# expansion.net
KiCad netlist of a schematic drawn in EAGLE
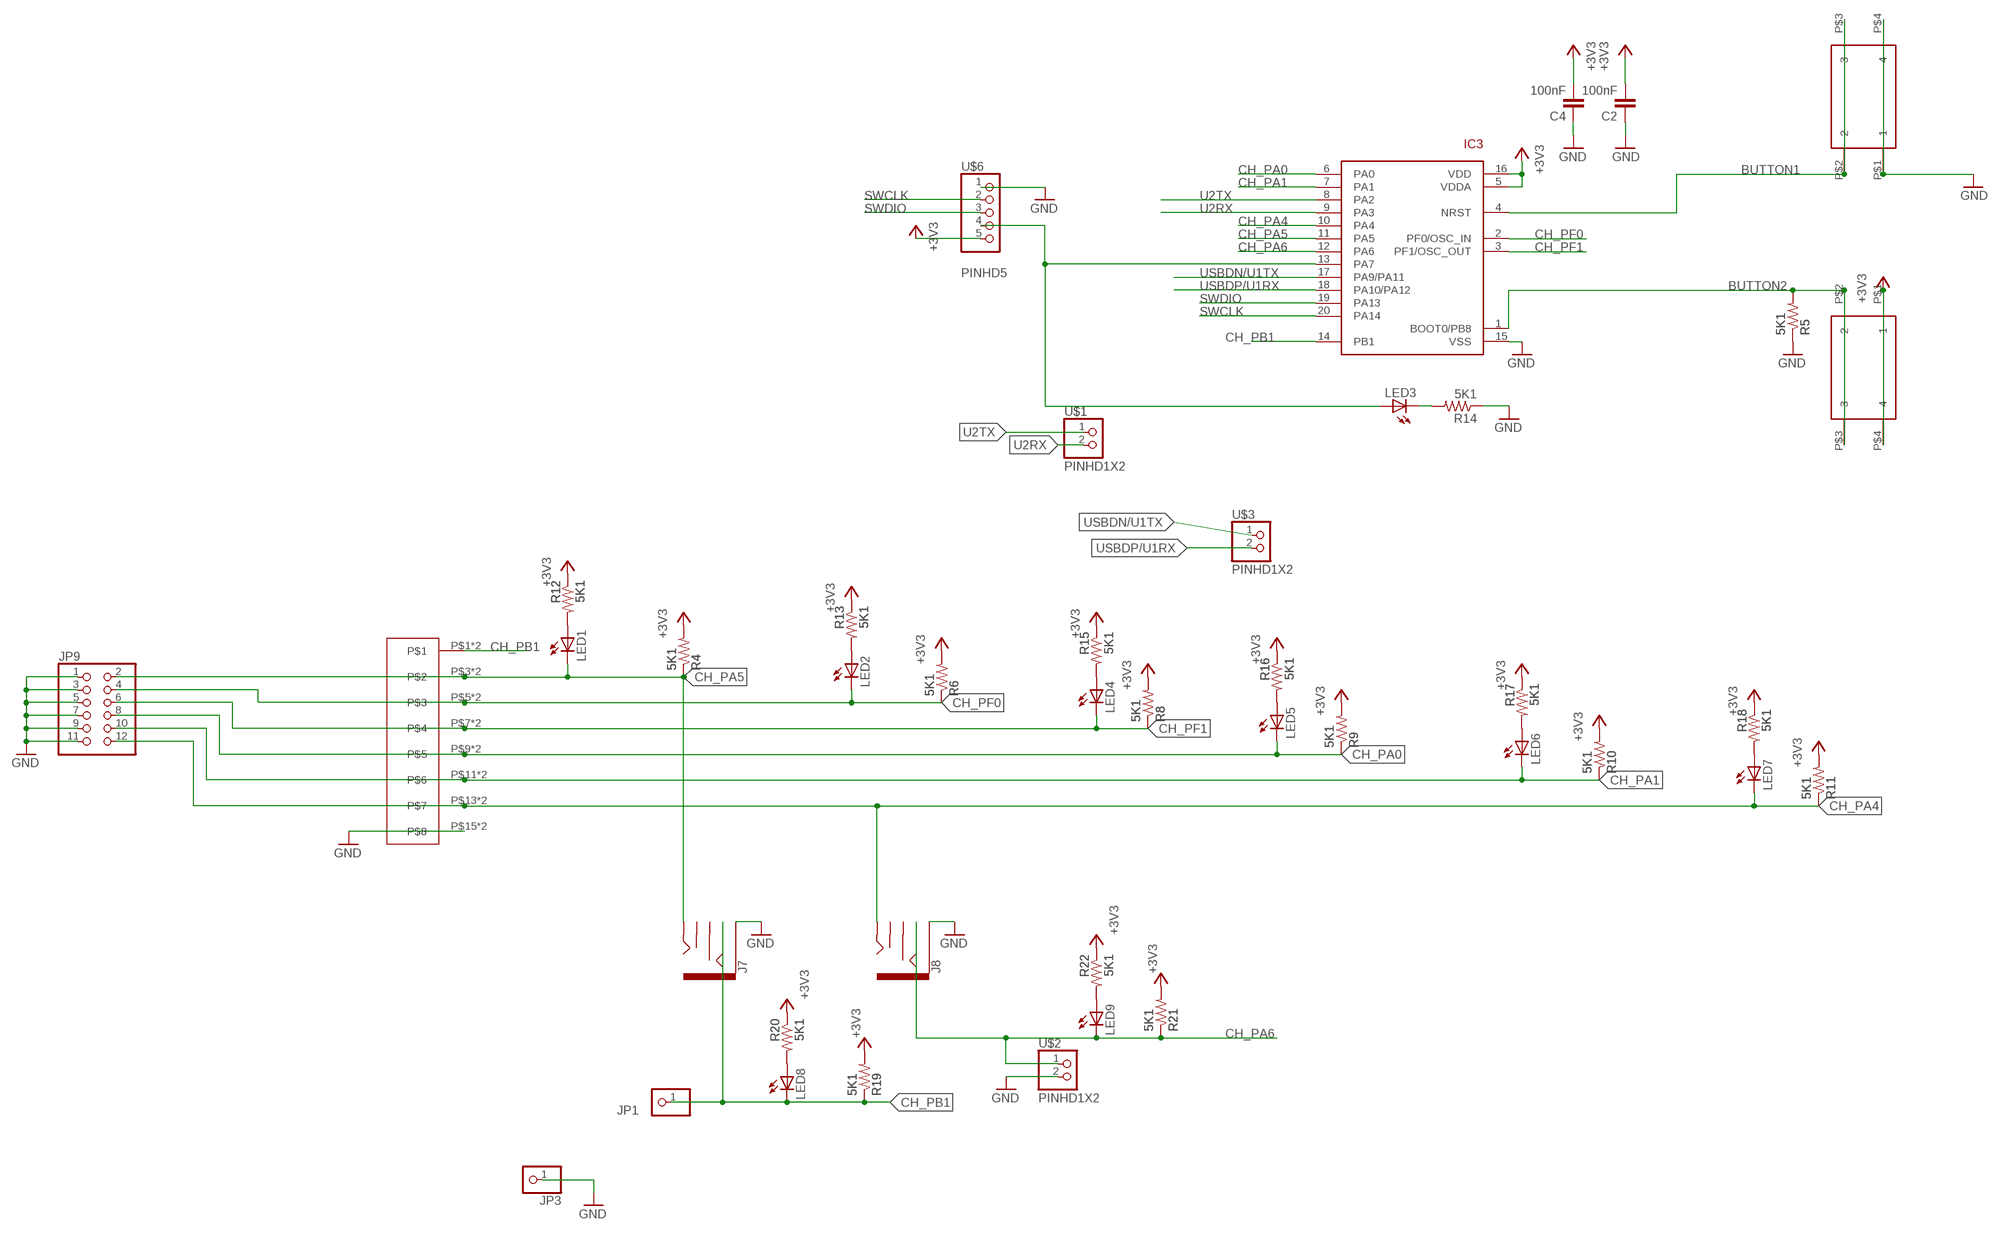
[diagram p0: schematic, sheet 1, part 1 of 2]
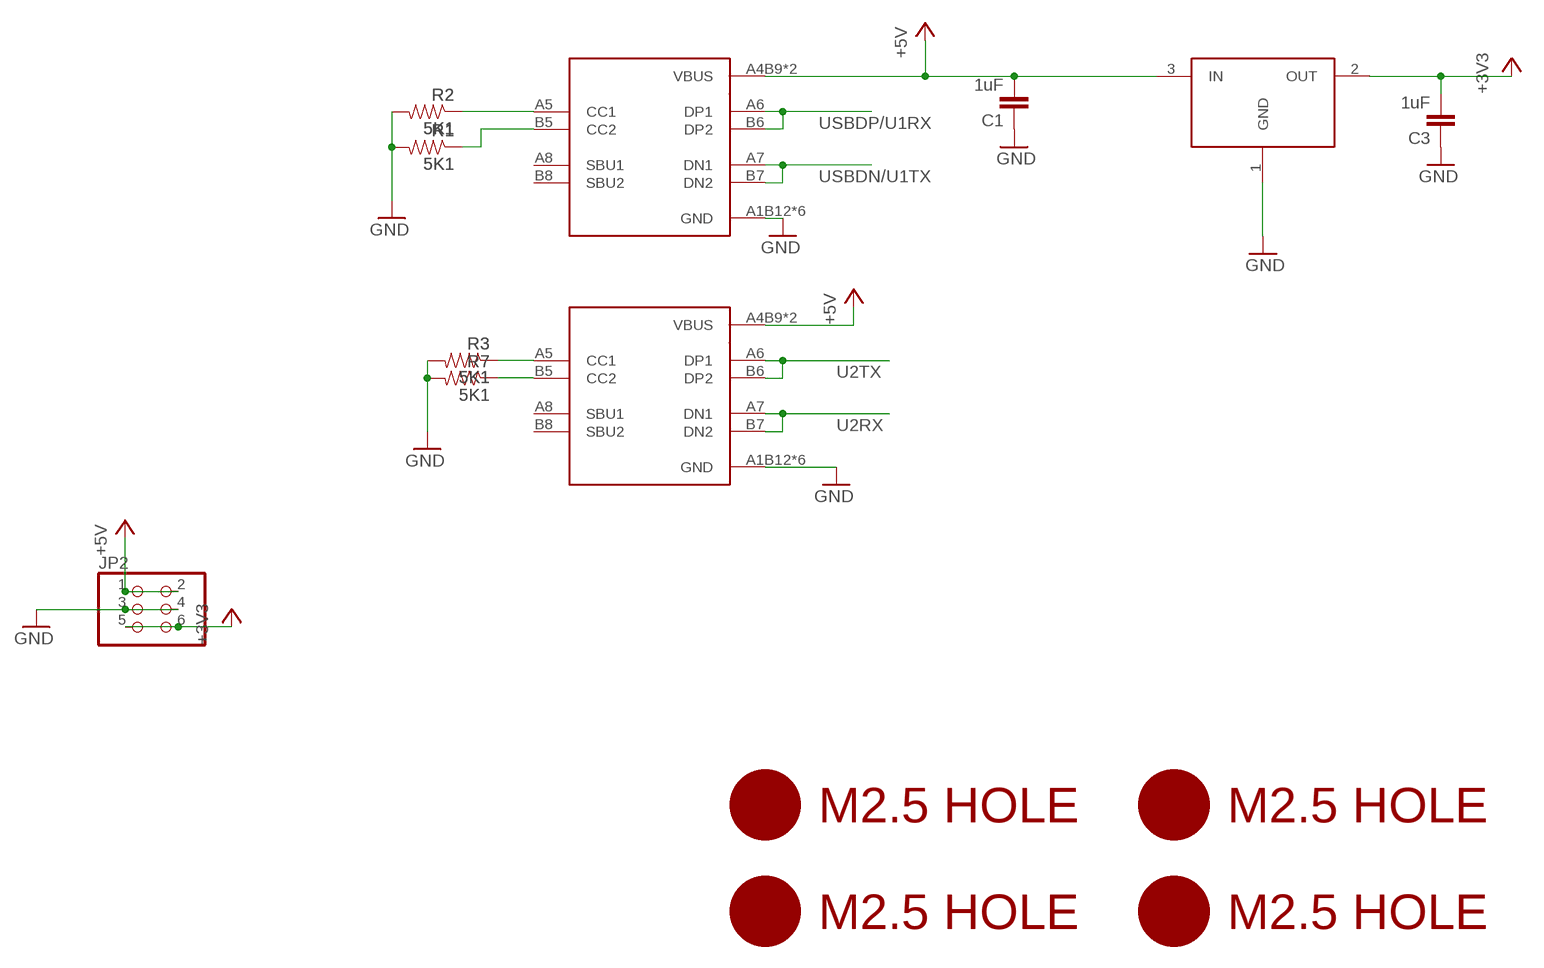
[diagram p1: schematic, sheet 1, part 2 of 2]

(export (version "E")
  (design (tool "Eeschema 10.0.6"))
  (components
    (comp (ref "C1")
      (value "1uF")
      (footprint "eagle-import:0805")
      (libsource (lib "eagle-import") (part "CAP0805"))
    )
    (comp (ref "C2")
      (value "100nF")
      (footprint "eagle-import:0805")
      (libsource (lib "eagle-import") (part "CAP0805"))
    )
    (comp (ref "C3")
      (value "1uF")
      (footprint "eagle-import:0805")
      (libsource (lib "eagle-import") (part "CAP0805"))
    )
    (comp (ref "C4")
      (value "100nF")
      (footprint "eagle-import:0805")
      (libsource (lib "eagle-import") (part "CAP0805"))
    )
    (comp (ref "IC3")
      (value "STM32F042F4")
      (footprint "eagle-import:TSSOP20")
      (libsource (lib "eagle-import") (part "STM32F042F4"))
    )
    (comp (ref "J7")
      (value "AUDIO_JACK_3.5MM_PTH")
      (footprint "eagle-import:AUDIO-JACK")
      (libsource (lib "eagle-import") (part "AUDIO_JACK_3.5MM_PTH"))
    )
    (comp (ref "J8")
      (value "AUDIO_JACK_3.5MM_PTH")
      (footprint "eagle-import:AUDIO-JACK")
      (libsource (lib "eagle-import") (part "AUDIO_JACK_3.5MM_PTH"))
    )
    (comp (ref "JP1")
      (value "PINHD-1X1")
      (footprint "eagle-import:1X01")
      (libsource (lib "eagle-import") (part "PINHD-1X1"))
    )
    (comp (ref "JP2")
      (value "PINHD-2X3")
      (footprint "eagle-import:2X03")
      (libsource (lib "eagle-import") (part "PINHD-2X3"))
    )
    (comp (ref "JP3")
      (value "PINHD-1X1")
      (footprint "eagle-import:1X01")
      (libsource (lib "eagle-import") (part "PINHD-1X1"))
    )
    (comp (ref "JP9")
      (value "PINHD-2X6")
      (footprint "eagle-import:2X06")
      (libsource (lib "eagle-import") (part "PINHD-2X6"))
    )
    (comp (ref "LED1")
      (value "LEDCHIP-LED0805")
      (footprint "eagle-import:CHIP-LED0805")
      (libsource (lib "eagle-import") (part "LEDCHIP-LED0805"))
    )
    (comp (ref "LED2")
      (value "LEDCHIP-LED0805")
      (footprint "eagle-import:CHIP-LED0805")
      (libsource (lib "eagle-import") (part "LEDCHIP-LED0805"))
    )
    (comp (ref "LED3")
      (value "LEDCHIP-LED0805")
      (footprint "eagle-import:CHIP-LED0805")
      (libsource (lib "eagle-import") (part "LEDCHIP-LED0805"))
    )
    (comp (ref "LED4")
      (value "LEDCHIP-LED0805")
      (footprint "eagle-import:CHIP-LED0805")
      (libsource (lib "eagle-import") (part "LEDCHIP-LED0805"))
    )
    (comp (ref "LED5")
      (value "LEDCHIP-LED0805")
      (footprint "eagle-import:CHIP-LED0805")
      (libsource (lib "eagle-import") (part "LEDCHIP-LED0805"))
    )
    (comp (ref "LED6")
      (value "LEDCHIP-LED0805")
      (footprint "eagle-import:CHIP-LED0805")
      (libsource (lib "eagle-import") (part "LEDCHIP-LED0805"))
    )
    (comp (ref "LED7")
      (value "LEDCHIP-LED0805")
      (footprint "eagle-import:CHIP-LED0805")
      (libsource (lib "eagle-import") (part "LEDCHIP-LED0805"))
    )
    (comp (ref "LED8")
      (value "LEDCHIP-LED0805")
      (footprint "eagle-import:CHIP-LED0805")
      (libsource (lib "eagle-import") (part "LEDCHIP-LED0805"))
    )
    (comp (ref "LED9")
      (value "LEDCHIP-LED0805")
      (footprint "eagle-import:CHIP-LED0805")
      (libsource (lib "eagle-import") (part "LEDCHIP-LED0805"))
    )
    (comp (ref "R1")
      (value "5K1")
      (footprint "eagle-import:0805")
      (libsource (lib "eagle-import") (part "joyAnalog_RESISTOR0805-RES"))
    )
    (comp (ref "R2")
      (value "5K1")
      (footprint "eagle-import:0805")
      (libsource (lib "eagle-import") (part "joyAnalog_RESISTOR0805-RES"))
    )
    (comp (ref "R3")
      (value "5K1")
      (footprint "eagle-import:0805")
      (libsource (lib "eagle-import") (part "joyAnalog_RESISTOR0805-RES"))
    )
    (comp (ref "R4")
      (value "5K1")
      (footprint "eagle-import:0805")
      (libsource (lib "eagle-import") (part "joyAnalog_RESISTOR0805-RES"))
    )
    (comp (ref "R5")
      (value "5K1")
      (footprint "eagle-import:0805")
      (libsource (lib "eagle-import") (part "joyAnalog_RESISTOR0805-RES"))
    )
    (comp (ref "R6")
      (value "5K1")
      (footprint "eagle-import:0805")
      (libsource (lib "eagle-import") (part "joyAnalog_RESISTOR0805-RES"))
    )
    (comp (ref "R7")
      (value "5K1")
      (footprint "eagle-import:0805")
      (libsource (lib "eagle-import") (part "joyAnalog_RESISTOR0805-RES"))
    )
    (comp (ref "R8")
      (value "5K1")
      (footprint "eagle-import:0805")
      (libsource (lib "eagle-import") (part "joyAnalog_RESISTOR0805-RES"))
    )
    (comp (ref "R9")
      (value "5K1")
      (footprint "eagle-import:0805")
      (libsource (lib "eagle-import") (part "joyAnalog_RESISTOR0805-RES"))
    )
    (comp (ref "R10")
      (value "5K1")
      (footprint "eagle-import:0805")
      (libsource (lib "eagle-import") (part "joyAnalog_RESISTOR0805-RES"))
    )
    (comp (ref "R11")
      (value "5K1")
      (footprint "eagle-import:0805")
      (libsource (lib "eagle-import") (part "joyAnalog_RESISTOR0805-RES"))
    )
    (comp (ref "R12")
      (value "5K1")
      (footprint "eagle-import:0805")
      (libsource (lib "eagle-import") (part "joyAnalog_RESISTOR0805-RES"))
    )
    (comp (ref "R13")
      (value "5K1")
      (footprint "eagle-import:0805")
      (libsource (lib "eagle-import") (part "joyAnalog_RESISTOR0805-RES"))
    )
    (comp (ref "R14")
      (value "5K1")
      (footprint "eagle-import:0805")
      (libsource (lib "eagle-import") (part "RESISTOR0805-RES"))
    )
    (comp (ref "R15")
      (value "5K1")
      (footprint "eagle-import:0805")
      (libsource (lib "eagle-import") (part "joyAnalog_RESISTOR0805-RES"))
    )
    (comp (ref "R16")
      (value "5K1")
      (footprint "eagle-import:0805")
      (libsource (lib "eagle-import") (part "joyAnalog_RESISTOR0805-RES"))
    )
    (comp (ref "R17")
      (value "5K1")
      (footprint "eagle-import:0805")
      (libsource (lib "eagle-import") (part "joyAnalog_RESISTOR0805-RES"))
    )
    (comp (ref "R18")
      (value "5K1")
      (footprint "eagle-import:0805")
      (libsource (lib "eagle-import") (part "joyAnalog_RESISTOR0805-RES"))
    )
    (comp (ref "R19")
      (value "5K1")
      (footprint "eagle-import:0805")
      (libsource (lib "eagle-import") (part "joyAnalog_RESISTOR0805-RES"))
    )
    (comp (ref "R20")
      (value "5K1")
      (footprint "eagle-import:0805")
      (libsource (lib "eagle-import") (part "joyAnalog_RESISTOR0805-RES"))
    )
    (comp (ref "R21")
      (value "5K1")
      (footprint "eagle-import:0805")
      (libsource (lib "eagle-import") (part "joyAnalog_RESISTOR0805-RES"))
    )
    (comp (ref "R22")
      (value "5K1")
      (footprint "eagle-import:0805")
      (libsource (lib "eagle-import") (part "joyAnalog_RESISTOR0805-RES"))
    )
    (comp (ref "SW3")
      (value "324_SW")
      (footprint "eagle-import:342_SWICH_FOOT")
      (libsource (lib "eagle-import") (part "324_SW"))
    )
    (comp (ref "SW4")
      (value "324_SW")
      (footprint "eagle-import:342_SWICH_FOOT")
      (libsource (lib "eagle-import") (part "324_SW"))
    )
    (comp (ref "U$1")
      (value "PINHD1X2")
      (footprint "eagle-import:1X02")
      (libsource (lib "eagle-import") (part "PINHD1X2"))
    )
    (comp (ref "U$2")
      (value "PINHD1X2")
      (footprint "eagle-import:1X02")
      (libsource (lib "eagle-import") (part "PINHD1X2"))
    )
    (comp (ref "U$3")
      (value "PINHD1X2")
      (footprint "eagle-import:1X02")
      (libsource (lib "eagle-import") (part "PINHD1X2"))
    )
    (comp (ref "U$6")
      (value "PINHD5")
      (footprint "eagle-import:1X05")
      (libsource (lib "eagle-import") (part "PINHD5"))
    )
    (comp (ref "U$8")
      (value "M2.5HOLE")
      (footprint "eagle-import:M2.5HOLE")
      (libsource (lib "eagle-import") (part "M2.5HOLE"))
    )
    (comp (ref "U$9")
      (value "M2.5HOLE")
      (footprint "eagle-import:M2.5HOLE")
      (libsource (lib "eagle-import") (part "M2.5HOLE"))
    )
    (comp (ref "U$10")
      (value "M2.5HOLE")
      (footprint "eagle-import:M2.5HOLE")
      (libsource (lib "eagle-import") (part "M2.5HOLE"))
    )
    (comp (ref "U$11")
      (value "M2.5HOLE")
      (footprint "eagle-import:M2.5HOLE")
      (libsource (lib "eagle-import") (part "M2.5HOLE"))
    )
    (comp (ref "U$14")
      (value "DG2204R-5.0-8DG2204-8")
      (footprint "eagle-import:DG2204R-8-THERMAL")
      (libsource (lib "eagle-import") (part "DG2204R-5.0-8DG2204-8"))
    )
    (comp (ref "U1")
      (value "USBC_16P")
      (footprint "eagle-import:USBC_16P_FOOT")
      (libsource (lib "eagle-import") (part "USBC_16P"))
    )
    (comp (ref "U2")
      (value "USBC_16P")
      (footprint "eagle-import:USBC_16P_FOOT")
      (libsource (lib "eagle-import") (part "USBC_16P"))
    )
    (comp (ref "U4")
      (value "XC6206_DEV")
      (footprint "eagle-import:SOT23R_INFINEON")
      (libsource (lib "eagle-import") (part "XC6206_DEV"))
    )
  )
  (nets
    (net (code "1") (name "+3V3") (class "Default")
      (node (ref "C2") (pin "2") (pinfunction "2_2") (pintype "passive"))
      (node (ref "C3") (pin "2") (pinfunction "2_2") (pintype "passive"))
      (node (ref "C4") (pin "2") (pinfunction "2_2") (pintype "passive"))
      (node (ref "IC3") (pin "16") (pinfunction "VDD_16") (pintype "bidirectional"))
      (node (ref "IC3") (pin "5") (pinfunction "VDDA_5") (pintype "bidirectional"))
      (node (ref "JP2") (pin "5") (pinfunction "5_5") (pintype "passive"))
      (node (ref "JP2") (pin "6") (pinfunction "6_6") (pintype "passive"))
      (node (ref "R10") (pin "2") (pinfunction "2_2") (pintype "passive"))
      (node (ref "R11") (pin "2") (pinfunction "2_2") (pintype "passive"))
      (node (ref "R12") (pin "1") (pinfunction "1_1") (pintype "passive"))
      (node (ref "R13") (pin "1") (pinfunction "1_1") (pintype "passive"))
      (node (ref "R15") (pin "1") (pinfunction "1_1") (pintype "passive"))
      (node (ref "R16") (pin "1") (pinfunction "1_1") (pintype "passive"))
      (node (ref "R17") (pin "1") (pinfunction "1_1") (pintype "passive"))
      (node (ref "R18") (pin "1") (pinfunction "1_1") (pintype "passive"))
      (node (ref "R19") (pin "2") (pinfunction "2_2") (pintype "passive"))
      (node (ref "R20") (pin "1") (pinfunction "1_1") (pintype "passive"))
      (node (ref "R21") (pin "2") (pinfunction "2_2") (pintype "passive"))
      (node (ref "R22") (pin "1") (pinfunction "1_1") (pintype "passive"))
      (node (ref "R4") (pin "2") (pinfunction "2_2") (pintype "passive"))
      (node (ref "R6") (pin "2") (pinfunction "2_2") (pintype "passive"))
      (node (ref "R8") (pin "2") (pinfunction "2_2") (pintype "passive"))
      (node (ref "R9") (pin "2") (pinfunction "2_2") (pintype "passive"))
      (node (ref "SW4") (pin "P$1") (pinfunction "1_P$1") (pintype "bidirectional"))
      (node (ref "SW4") (pin "P$4") (pinfunction "4_P$4") (pintype "bidirectional"))
      (node (ref "U$6") (pin "5") (pinfunction "5_5") (pintype "passive"))
      (node (ref "U4") (pin "2") (pinfunction "OUT_2") (pintype "bidirectional"))
    )
    (net (code "2") (name "+5V") (class "Default")
      (node (ref "C1") (pin "2") (pinfunction "2_2") (pintype "passive"))
      (node (ref "JP2") (pin "1") (pinfunction "1_1") (pintype "passive"))
      (node (ref "JP2") (pin "2") (pinfunction "2_2") (pintype "passive"))
      (node (ref "U1") (pin "A4B9") (pinfunction "VBUS_A4B9") (pintype "bidirectional"))
      (node (ref "U1") (pin "B4A9") (pinfunction "VBUS_B4A9") (pintype "bidirectional"))
      (node (ref "U2") (pin "A4B9") (pinfunction "VBUS_A4B9") (pintype "bidirectional"))
      (node (ref "U2") (pin "B4A9") (pinfunction "VBUS_B4A9") (pintype "bidirectional"))
      (node (ref "U4") (pin "3") (pinfunction "IN_3") (pintype "bidirectional"))
    )
    (net (code "3") (name "/BUTTON1") (class "Default")
      (node (ref "IC3") (pin "4") (pinfunction "NRST_4") (pintype "bidirectional"))
      (node (ref "SW3") (pin "P$2") (pinfunction "2_P$2") (pintype "bidirectional"))
      (node (ref "SW3") (pin "P$3") (pinfunction "3_P$3") (pintype "bidirectional"))
    )
    (net (code "4") (name "/BUTTON2") (class "Default")
      (node (ref "IC3") (pin "1") (pinfunction "BOOT0/PB8_1") (pintype "bidirectional"))
      (node (ref "R5") (pin "2") (pinfunction "2_2") (pintype "passive"))
      (node (ref "SW4") (pin "P$2") (pinfunction "2_P$2") (pintype "bidirectional"))
      (node (ref "SW4") (pin "P$3") (pinfunction "3_P$3") (pintype "bidirectional"))
    )
    (net (code "5") (name "/CH_PA6") (class "Default")
      (node (ref "IC3") (pin "12") (pinfunction "PA6_12") (pintype "bidirectional"))
      (node (ref "J8") (pin "RING") (pinfunction "RING_RING") (pintype "bidirectional"))
      (node (ref "LED9") (pin "C") (pinfunction "C_C") (pintype "passive"))
      (node (ref "R21") (pin "1") (pinfunction "1_1") (pintype "passive"))
      (node (ref "U$2") (pin "1") (pinfunction "1_1") (pintype "passive"))
    )
    (net (code "6") (name "/SWCLK") (class "Default")
      (node (ref "IC3") (pin "20") (pinfunction "PA14_20") (pintype "bidirectional"))
      (node (ref "U$6") (pin "2") (pinfunction "2_2") (pintype "passive"))
    )
    (net (code "7") (name "/SWDIO") (class "Default")
      (node (ref "IC3") (pin "19") (pinfunction "PA13_19") (pintype "bidirectional"))
      (node (ref "U$6") (pin "3") (pinfunction "3_3") (pintype "passive"))
    )
    (net (code "8") (name "CH_PA0") (class "Default")
      (node (ref "IC3") (pin "6") (pinfunction "PA0_6") (pintype "bidirectional"))
      (node (ref "JP9") (pin "8") (pinfunction "8_8") (pintype "passive"))
      (node (ref "LED5") (pin "C") (pinfunction "C_C") (pintype "passive"))
      (node (ref "R9") (pin "1") (pinfunction "1_1") (pintype "passive"))
      (node (ref "U$14") (pin "P$10") (pinfunction "P$5_P$10") (pintype "bidirectional"))
      (node (ref "U$14") (pin "P$9") (pinfunction "P$5_P$9") (pintype "bidirectional"))
    )
    (net (code "9") (name "CH_PA1") (class "Default")
      (node (ref "IC3") (pin "7") (pinfunction "PA1_7") (pintype "bidirectional"))
      (node (ref "JP9") (pin "10") (pinfunction "10_10") (pintype "passive"))
      (node (ref "LED6") (pin "C") (pinfunction "C_C") (pintype "passive"))
      (node (ref "R10") (pin "1") (pinfunction "1_1") (pintype "passive"))
      (node (ref "U$14") (pin "P$11") (pinfunction "P$6_P$11") (pintype "bidirectional"))
      (node (ref "U$14") (pin "P$12") (pinfunction "P$6_P$12") (pintype "bidirectional"))
    )
    (net (code "10") (name "CH_PA4") (class "Default")
      (node (ref "IC3") (pin "10") (pinfunction "PA4_10") (pintype "bidirectional"))
      (node (ref "J8") (pin "TIP") (pinfunction "TIP_TIP") (pintype "bidirectional"))
      (node (ref "JP9") (pin "12") (pinfunction "12_12") (pintype "passive"))
      (node (ref "LED7") (pin "C") (pinfunction "C_C") (pintype "passive"))
      (node (ref "R11") (pin "1") (pinfunction "1_1") (pintype "passive"))
      (node (ref "U$14") (pin "P$13") (pinfunction "P$7_P$13") (pintype "bidirectional"))
      (node (ref "U$14") (pin "P$14") (pinfunction "P$7_P$14") (pintype "bidirectional"))
    )
    (net (code "11") (name "CH_PA5") (class "Default")
      (node (ref "IC3") (pin "11") (pinfunction "PA5_11") (pintype "bidirectional"))
      (node (ref "J7") (pin "TIP") (pinfunction "TIP_TIP") (pintype "bidirectional"))
      (node (ref "JP9") (pin "2") (pinfunction "2_2") (pintype "passive"))
      (node (ref "LED1") (pin "C") (pinfunction "C_C") (pintype "passive"))
      (node (ref "R4") (pin "1") (pinfunction "1_1") (pintype "passive"))
      (node (ref "U$14") (pin "P$3") (pinfunction "P$2_P$3") (pintype "bidirectional"))
      (node (ref "U$14") (pin "P$4") (pinfunction "P$2_P$4") (pintype "bidirectional"))
    )
    (net (code "12") (name "CH_PB1") (class "Default")
      (node (ref "IC3") (pin "14") (pinfunction "PB1_14") (pintype "bidirectional"))
      (node (ref "J7") (pin "RING") (pinfunction "RING_RING") (pintype "bidirectional"))
      (node (ref "JP1") (pin "1") (pinfunction "1_1") (pintype "passive"))
      (node (ref "LED8") (pin "C") (pinfunction "C_C") (pintype "passive"))
      (node (ref "R19") (pin "1") (pinfunction "1_1") (pintype "passive"))
      (node (ref "U$14") (pin "P$1") (pinfunction "P$1_P$1") (pintype "bidirectional"))
      (node (ref "U$14") (pin "P$2") (pinfunction "P$1_P$2") (pintype "bidirectional"))
    )
    (net (code "13") (name "CH_PF0") (class "Default")
      (node (ref "IC3") (pin "2") (pinfunction "PF0/OSC_IN_2") (pintype "bidirectional"))
      (node (ref "JP9") (pin "4") (pinfunction "4_4") (pintype "passive"))
      (node (ref "LED2") (pin "C") (pinfunction "C_C") (pintype "passive"))
      (node (ref "R6") (pin "1") (pinfunction "1_1") (pintype "passive"))
      (node (ref "U$14") (pin "P$5") (pinfunction "P$3_P$5") (pintype "bidirectional"))
      (node (ref "U$14") (pin "P$6") (pinfunction "P$3_P$6") (pintype "bidirectional"))
    )
    (net (code "14") (name "CH_PF1") (class "Default")
      (node (ref "IC3") (pin "3") (pinfunction "PF1/OSC_OUT_3") (pintype "bidirectional"))
      (node (ref "JP9") (pin "6") (pinfunction "6_6") (pintype "passive"))
      (node (ref "LED4") (pin "C") (pinfunction "C_C") (pintype "passive"))
      (node (ref "R8") (pin "1") (pinfunction "1_1") (pintype "passive"))
      (node (ref "U$14") (pin "P$7") (pinfunction "P$4_P$7") (pintype "bidirectional"))
      (node (ref "U$14") (pin "P$8") (pinfunction "P$4_P$8") (pintype "bidirectional"))
    )
    (net (code "15") (name "GND") (class "Default")
      (node (ref "C1") (pin "1") (pinfunction "1_1") (pintype "passive"))
      (node (ref "C2") (pin "1") (pinfunction "1_1") (pintype "passive"))
      (node (ref "C3") (pin "1") (pinfunction "1_1") (pintype "passive"))
      (node (ref "C4") (pin "1") (pinfunction "1_1") (pintype "passive"))
      (node (ref "IC3") (pin "15") (pinfunction "VSS_15") (pintype "bidirectional"))
      (node (ref "J7") (pin "SLEEVE") (pinfunction "SLEEVE_SLEEVE") (pintype "bidirectional"))
      (node (ref "J8") (pin "SLEEVE") (pinfunction "SLEEVE_SLEEVE") (pintype "bidirectional"))
      (node (ref "JP2") (pin "3") (pinfunction "3_3") (pintype "passive"))
      (node (ref "JP2") (pin "4") (pinfunction "4_4") (pintype "passive"))
      (node (ref "JP3") (pin "1") (pinfunction "1_1") (pintype "passive"))
      (node (ref "JP9") (pin "1") (pinfunction "1_1") (pintype "passive"))
      (node (ref "JP9") (pin "11") (pinfunction "11_11") (pintype "passive"))
      (node (ref "JP9") (pin "3") (pinfunction "3_3") (pintype "passive"))
      (node (ref "JP9") (pin "5") (pinfunction "5_5") (pintype "passive"))
      (node (ref "JP9") (pin "7") (pinfunction "7_7") (pintype "passive"))
      (node (ref "JP9") (pin "9") (pinfunction "9_9") (pintype "passive"))
      (node (ref "R1") (pin "2") (pinfunction "2_2") (pintype "passive"))
      (node (ref "R14") (pin "1") (pinfunction "1_1") (pintype "passive"))
      (node (ref "R2") (pin "2") (pinfunction "2_2") (pintype "passive"))
      (node (ref "R3") (pin "2") (pinfunction "2_2") (pintype "passive"))
      (node (ref "R5") (pin "1") (pinfunction "1_1") (pintype "passive"))
      (node (ref "R7") (pin "2") (pinfunction "2_2") (pintype "passive"))
      (node (ref "SW3") (pin "P$1") (pinfunction "1_P$1") (pintype "bidirectional"))
      (node (ref "SW3") (pin "P$4") (pinfunction "4_P$4") (pintype "bidirectional"))
      (node (ref "U$14") (pin "P$15") (pinfunction "P$8_P$15") (pintype "bidirectional"))
      (node (ref "U$14") (pin "P$16") (pinfunction "P$8_P$16") (pintype "bidirectional"))
      (node (ref "U$2") (pin "2") (pinfunction "2_2") (pintype "passive"))
      (node (ref "U$6") (pin "1") (pinfunction "1_1") (pintype "passive"))
      (node (ref "U1") (pin "A1B12") (pinfunction "GND_A1B12") (pintype "bidirectional"))
      (node (ref "U1") (pin "B11A12") (pinfunction "GND_B11A12") (pintype "bidirectional"))
      (node (ref "U1") (pin "P$13") (pinfunction "GND_P$13") (pintype "bidirectional"))
      (node (ref "U1") (pin "P$14") (pinfunction "GND_P$14") (pintype "bidirectional"))
      (node (ref "U1") (pin "P$15") (pinfunction "GND_P$15") (pintype "bidirectional"))
      (node (ref "U1") (pin "P$16") (pinfunction "GND_P$16") (pintype "bidirectional"))
      (node (ref "U2") (pin "A1B12") (pinfunction "GND_A1B12") (pintype "bidirectional"))
      (node (ref "U2") (pin "B11A12") (pinfunction "GND_B11A12") (pintype "bidirectional"))
      (node (ref "U2") (pin "P$13") (pinfunction "GND_P$13") (pintype "bidirectional"))
      (node (ref "U2") (pin "P$14") (pinfunction "GND_P$14") (pintype "bidirectional"))
      (node (ref "U2") (pin "P$15") (pinfunction "GND_P$15") (pintype "bidirectional"))
      (node (ref "U2") (pin "P$16") (pinfunction "GND_P$16") (pintype "bidirectional"))
      (node (ref "U4") (pin "1") (pinfunction "GND_1") (pintype "bidirectional"))
    )
    (net (code "16") (name "Net-(IC3-PA7)") (class "Default")
      (node (ref "IC3") (pin "13") (pinfunction "PA7_13") (pintype "bidirectional"))
      (node (ref "LED3") (pin "A") (pinfunction "A_A") (pintype "passive"))
      (node (ref "U$6") (pin "4") (pinfunction "4_4") (pintype "passive"))
    )
    (net (code "17") (name "Net-(LED1-PadA)") (class "Default")
      (node (ref "LED1") (pin "A") (pinfunction "A_A") (pintype "passive"))
      (node (ref "R12") (pin "2") (pinfunction "2_2") (pintype "passive"))
    )
    (net (code "18") (name "Net-(LED2-PadA)") (class "Default")
      (node (ref "LED2") (pin "A") (pinfunction "A_A") (pintype "passive"))
      (node (ref "R13") (pin "2") (pinfunction "2_2") (pintype "passive"))
    )
    (net (code "19") (name "Net-(LED3-PadC)") (class "Default")
      (node (ref "LED3") (pin "C") (pinfunction "C_C") (pintype "passive"))
      (node (ref "R14") (pin "2") (pinfunction "2_2") (pintype "passive"))
    )
    (net (code "20") (name "Net-(LED4-PadA)") (class "Default")
      (node (ref "LED4") (pin "A") (pinfunction "A_A") (pintype "passive"))
      (node (ref "R15") (pin "2") (pinfunction "2_2") (pintype "passive"))
    )
    (net (code "21") (name "Net-(LED5-PadA)") (class "Default")
      (node (ref "LED5") (pin "A") (pinfunction "A_A") (pintype "passive"))
      (node (ref "R16") (pin "2") (pinfunction "2_2") (pintype "passive"))
    )
    (net (code "22") (name "Net-(LED6-PadA)") (class "Default")
      (node (ref "LED6") (pin "A") (pinfunction "A_A") (pintype "passive"))
      (node (ref "R17") (pin "2") (pinfunction "2_2") (pintype "passive"))
    )
    (net (code "23") (name "Net-(LED7-PadA)") (class "Default")
      (node (ref "LED7") (pin "A") (pinfunction "A_A") (pintype "passive"))
      (node (ref "R18") (pin "2") (pinfunction "2_2") (pintype "passive"))
    )
    (net (code "24") (name "Net-(LED8-PadA)") (class "Default")
      (node (ref "LED8") (pin "A") (pinfunction "A_A") (pintype "passive"))
      (node (ref "R20") (pin "2") (pinfunction "2_2") (pintype "passive"))
    )
    (net (code "25") (name "Net-(LED9-PadA)") (class "Default")
      (node (ref "LED9") (pin "A") (pinfunction "A_A") (pintype "passive"))
      (node (ref "R22") (pin "2") (pinfunction "2_2") (pintype "passive"))
    )
    (net (code "26") (name "Net-(U1-CC1)") (class "Default")
      (node (ref "R3") (pin "1") (pinfunction "1_1") (pintype "passive"))
      (node (ref "U1") (pin "A5") (pinfunction "CC1_A5") (pintype "bidirectional"))
    )
    (net (code "27") (name "Net-(U1-CC2)") (class "Default")
      (node (ref "R7") (pin "1") (pinfunction "1_1") (pintype "passive"))
      (node (ref "U1") (pin "B5") (pinfunction "CC2_B5") (pintype "bidirectional"))
    )
    (net (code "28") (name "Net-(U2-CC1)") (class "Default")
      (node (ref "R2") (pin "1") (pinfunction "1_1") (pintype "passive"))
      (node (ref "U2") (pin "A5") (pinfunction "CC1_A5") (pintype "bidirectional"))
    )
    (net (code "29") (name "Net-(U2-CC2)") (class "Default")
      (node (ref "R1") (pin "1") (pinfunction "1_1") (pintype "passive"))
      (node (ref "U2") (pin "B5") (pinfunction "CC2_B5") (pintype "bidirectional"))
    )
    (net (code "30") (name "U2RX") (class "Default")
      (node (ref "IC3") (pin "9") (pinfunction "PA3_9") (pintype "bidirectional"))
      (node (ref "U$1") (pin "2") (pinfunction "2_2") (pintype "passive"))
      (node (ref "U1") (pin "A7") (pinfunction "DN1_A7") (pintype "bidirectional"))
      (node (ref "U1") (pin "B7") (pinfunction "DN2_B7") (pintype "bidirectional"))
    )
    (net (code "31") (name "U2TX") (class "Default")
      (node (ref "IC3") (pin "8") (pinfunction "PA2_8") (pintype "bidirectional"))
      (node (ref "U$1") (pin "1") (pinfunction "1_1") (pintype "passive"))
      (node (ref "U1") (pin "A6") (pinfunction "DP1_A6") (pintype "bidirectional"))
      (node (ref "U1") (pin "B6") (pinfunction "DP2_B6") (pintype "bidirectional"))
    )
    (net (code "32") (name "USBDN{slash}U1TX") (class "Default")
      (node (ref "IC3") (pin "17") (pinfunction "PA9/PA11_17") (pintype "bidirectional"))
      (node (ref "U$3") (pin "1") (pinfunction "1_1") (pintype "passive"))
      (node (ref "U2") (pin "A7") (pinfunction "DN1_A7") (pintype "bidirectional"))
      (node (ref "U2") (pin "B7") (pinfunction "DN2_B7") (pintype "bidirectional"))
    )
    (net (code "33") (name "USBDP{slash}U1RX") (class "Default")
      (node (ref "IC3") (pin "18") (pinfunction "PA10/PA12_18") (pintype "bidirectional"))
      (node (ref "U$3") (pin "2") (pinfunction "2_2") (pintype "passive"))
      (node (ref "U2") (pin "A6") (pinfunction "DP1_A6") (pintype "bidirectional"))
      (node (ref "U2") (pin "B6") (pinfunction "DP2_B6") (pintype "bidirectional"))
    )
    (net (code "34") (name "unconnected-(J7-PadRSH)") (class "Default")
      (node (ref "J7") (pin "RSH") (pinfunction "RSH_RSH") (pintype "bidirectional"))
    )
    (net (code "35") (name "unconnected-(J7-PadTSH)") (class "Default")
      (node (ref "J7") (pin "TSH") (pinfunction "TSH_TSH") (pintype "bidirectional"))
    )
    (net (code "36") (name "unconnected-(J8-PadRSH)") (class "Default")
      (node (ref "J8") (pin "RSH") (pinfunction "RSH_RSH") (pintype "bidirectional"))
    )
    (net (code "37") (name "unconnected-(J8-PadTSH)") (class "Default")
      (node (ref "J8") (pin "TSH") (pinfunction "TSH_TSH") (pintype "bidirectional"))
    )
    (net (code "38") (name "unconnected-(U1-SBU1-PadA8)") (class "Default")
      (node (ref "U1") (pin "A8") (pinfunction "SBU1_A8") (pintype "bidirectional"))
    )
    (net (code "39") (name "unconnected-(U1-SBU2-PadB8)") (class "Default")
      (node (ref "U1") (pin "B8") (pinfunction "SBU2_B8") (pintype "bidirectional"))
    )
    (net (code "40") (name "unconnected-(U2-SBU1-PadA8)") (class "Default")
      (node (ref "U2") (pin "A8") (pinfunction "SBU1_A8") (pintype "bidirectional"))
    )
    (net (code "41") (name "unconnected-(U2-SBU2-PadB8)") (class "Default")
      (node (ref "U2") (pin "B8") (pinfunction "SBU2_B8") (pintype "bidirectional"))
    )
  )
)
